# fanController.net
KiCad netlist of a schematic drawn in EAGLE
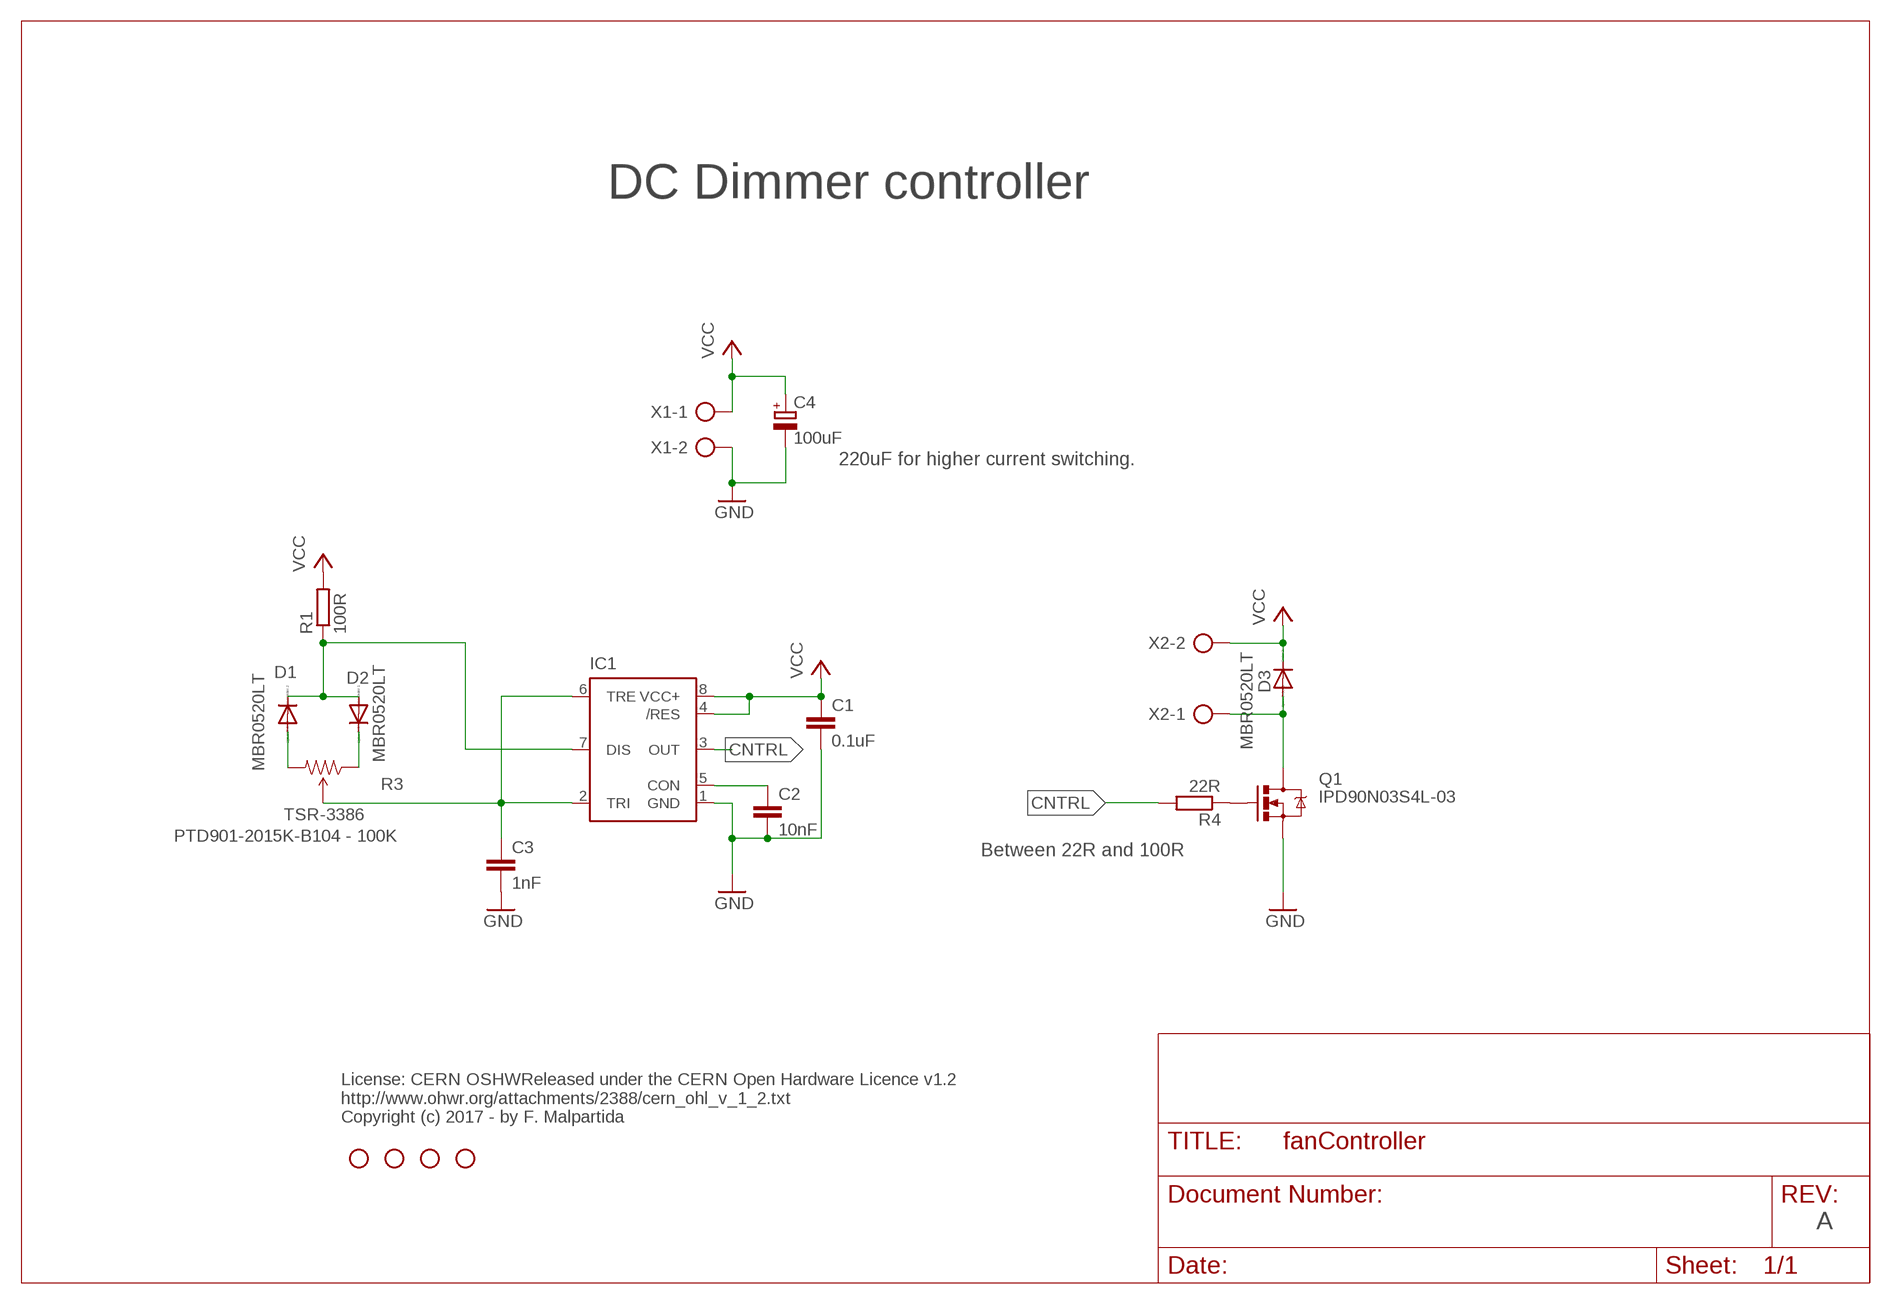
[diagram p0: schematic, sheet 1]

(export (version "E")
  (design (tool "Eeschema 10.0.6"))
  (components
    (comp (ref "C1")
      (value "0.1uF")
      (footprint "eagle-import:C0805")
      (libsource (lib "eagle-import") (part "C-EUC0805"))
    )
    (comp (ref "C2")
      (value "10nF")
      (footprint "eagle-import:C0805")
      (libsource (lib "eagle-import") (part "C-EUC0805"))
    )
    (comp (ref "C3")
      (value "1nF")
      (footprint "eagle-import:C0805")
      (libsource (lib "eagle-import") (part "C-EUC0805"))
    )
    (comp (ref "C4")
      (value "100uF")
      (footprint "eagle-import:PANASONIC_D")
      (libsource (lib "eagle-import") (part "CPOL-EUD"))
    )
    (comp (ref "D1")
      (value "MBR0520LT")
      (footprint "eagle-import:SOD123")
      (libsource (lib "eagle-import") (part "MBR0520LT"))
    )
    (comp (ref "D2")
      (value "MBR0520LT")
      (footprint "eagle-import:SOD123")
      (libsource (lib "eagle-import") (part "MBR0520LT"))
    )
    (comp (ref "D3")
      (value "MBR0520LT")
      (footprint "eagle-import:SOD123")
      (libsource (lib "eagle-import") (part "MBR0520LT"))
    )
    (comp (ref "IC1")
      (value "NE555D")
      (footprint "eagle-import:SO08")
      (libsource (lib "eagle-import") (part "NE555D"))
    )
    (comp (ref "Q1")
      (value "IPD90N03S4L-03")
      (footprint "eagle-import:DPAK")
      (libsource (lib "eagle-import") (part "MOSFET-NCHANNELFDD8780"))
    )
    (comp (ref "R1")
      (value "100R")
      (footprint "eagle-import:M0805")
      (libsource (lib "eagle-import") (part "R-EU_M0805"))
    )
    (comp (ref "R3")
      (value "TSR-3386")
      (footprint "eagle-import:3386U")
      (libsource (lib "eagle-import") (part "TRIMPOT-PTH-KNOB"))
    )
    (comp (ref "R4")
      (value "22R")
      (footprint "eagle-import:M0805")
      (libsource (lib "eagle-import") (part "R-EU_M0805"))
    )
    (comp (ref "STANDOFF1")
      (value "STAND-OFFTIGHT")
      (footprint "eagle-import:STAND-OFF-TIGHT")
      (libsource (lib "eagle-import") (part "STAND-OFFTIGHT"))
    )
    (comp (ref "STANDOFF2")
      (value "STAND-OFFTIGHT")
      (footprint "eagle-import:STAND-OFF-TIGHT")
      (libsource (lib "eagle-import") (part "STAND-OFFTIGHT"))
    )
    (comp (ref "STANDOFF3")
      (value "STAND-OFFTIGHT")
      (footprint "eagle-import:STAND-OFF-TIGHT")
      (libsource (lib "eagle-import") (part "STAND-OFFTIGHT"))
    )
    (comp (ref "STANDOFF4")
      (value "STAND-OFFTIGHT")
      (footprint "eagle-import:STAND-OFF-TIGHT")
      (libsource (lib "eagle-import") (part "STAND-OFFTIGHT"))
    )
    (comp (ref "X1")
      (value "AK500/2")
      (footprint "eagle-import:AK500_2")
      (libsource (lib "eagle-import") (part "AK500/2"))
    )
    (comp (ref "X2")
      (value "AK500/2")
      (footprint "eagle-import:AK500_2")
      (libsource (lib "eagle-import") (part "AK500/2"))
    )
  )
  (nets
    (net (code "1") (name "CNTRL") (class "Default")
      (node (ref "IC1") (pin "3") (pinfunction "OUT_3") (pintype "output"))
      (node (ref "R4") (pin "2") (pinfunction "2_2") (pintype "passive"))
    )
    (net (code "2") (name "GND") (class "Default")
      (node (ref "C1") (pin "2") (pinfunction "2_2") (pintype "passive"))
      (node (ref "C2") (pin "2") (pinfunction "2_2") (pintype "passive"))
      (node (ref "C3") (pin "2") (pinfunction "2_2") (pintype "passive"))
      (node (ref "C4") (pin "-") (pinfunction "-_-") (pintype "passive"))
      (node (ref "IC1") (pin "1") (pinfunction "GND_1") (pintype "power_in"))
      (node (ref "Q1") (pin "3") (pinfunction "S_3") (pintype "passive"))
      (node (ref "X1") (pin "2") (pinfunction "KL_2") (pintype "passive"))
    )
    (net (code "3") (name "Net-(IC1-CON)") (class "Default")
      (node (ref "C2") (pin "1") (pinfunction "1_1") (pintype "passive"))
      (node (ref "IC1") (pin "5") (pinfunction "CON_5") (pintype "input"))
    )
    (net (code "4") (name "Net-(IC1-DIS)") (class "Default")
      (node (ref "D1") (pin "C") (pinfunction "C_C") (pintype "passive"))
      (node (ref "D2") (pin "A") (pinfunction "A_A") (pintype "passive"))
      (node (ref "IC1") (pin "7") (pinfunction "DIS_7") (pintype "input"))
      (node (ref "R1") (pin "1") (pinfunction "1_1") (pintype "passive"))
    )
    (net (code "5") (name "Net-(IC1-TRE)") (class "Default")
      (node (ref "C3") (pin "1") (pinfunction "1_1") (pintype "passive"))
      (node (ref "IC1") (pin "2") (pinfunction "TRI_2") (pintype "input"))
      (node (ref "IC1") (pin "6") (pinfunction "TRE_6") (pintype "input"))
      (node (ref "R3") (pin "2") (pinfunction "WIPER_2") (pintype "passive"))
    )
    (net (code "6") (name "Net-(Q1-D)") (class "Default")
      (node (ref "D3") (pin "A") (pinfunction "A_A") (pintype "passive"))
      (node (ref "Q1") (pin "4") (pinfunction "D_4") (pintype "passive"))
      (node (ref "X2") (pin "1") (pinfunction "KL_1") (pintype "passive"))
    )
    (net (code "7") (name "Net-(Q1-G)") (class "Default")
      (node (ref "Q1") (pin "1") (pinfunction "G_1") (pintype "passive"))
      (node (ref "R4") (pin "1") (pinfunction "1_1") (pintype "passive"))
    )
    (net (code "8") (name "Net-(R3-CCW)") (class "Default")
      (node (ref "D2") (pin "C") (pinfunction "C_C") (pintype "passive"))
      (node (ref "R3") (pin "1") (pinfunction "CCW_1") (pintype "passive"))
    )
    (net (code "9") (name "Net-(R3-CW)") (class "Default")
      (node (ref "D1") (pin "A") (pinfunction "A_A") (pintype "passive"))
      (node (ref "R3") (pin "3") (pinfunction "CW_3") (pintype "passive"))
    )
    (net (code "10") (name "VCC") (class "Default")
      (node (ref "C1") (pin "1") (pinfunction "1_1") (pintype "passive"))
      (node (ref "C4") (pin "+") (pinfunction "+_+") (pintype "passive"))
      (node (ref "D3") (pin "C") (pinfunction "C_C") (pintype "passive"))
      (node (ref "IC1") (pin "4") (pinfunction "/RES_4") (pintype "input"))
      (node (ref "IC1") (pin "8") (pinfunction "VCC+_8") (pintype "power_in"))
      (node (ref "R1") (pin "2") (pinfunction "2_2") (pintype "passive"))
      (node (ref "X1") (pin "1") (pinfunction "KL_1") (pintype "passive"))
      (node (ref "X2") (pin "2") (pinfunction "KL_2") (pintype "passive"))
    )
  )
)
